# BackplanePowerSupply.net
KiCad netlist of a schematic drawn in EAGLE
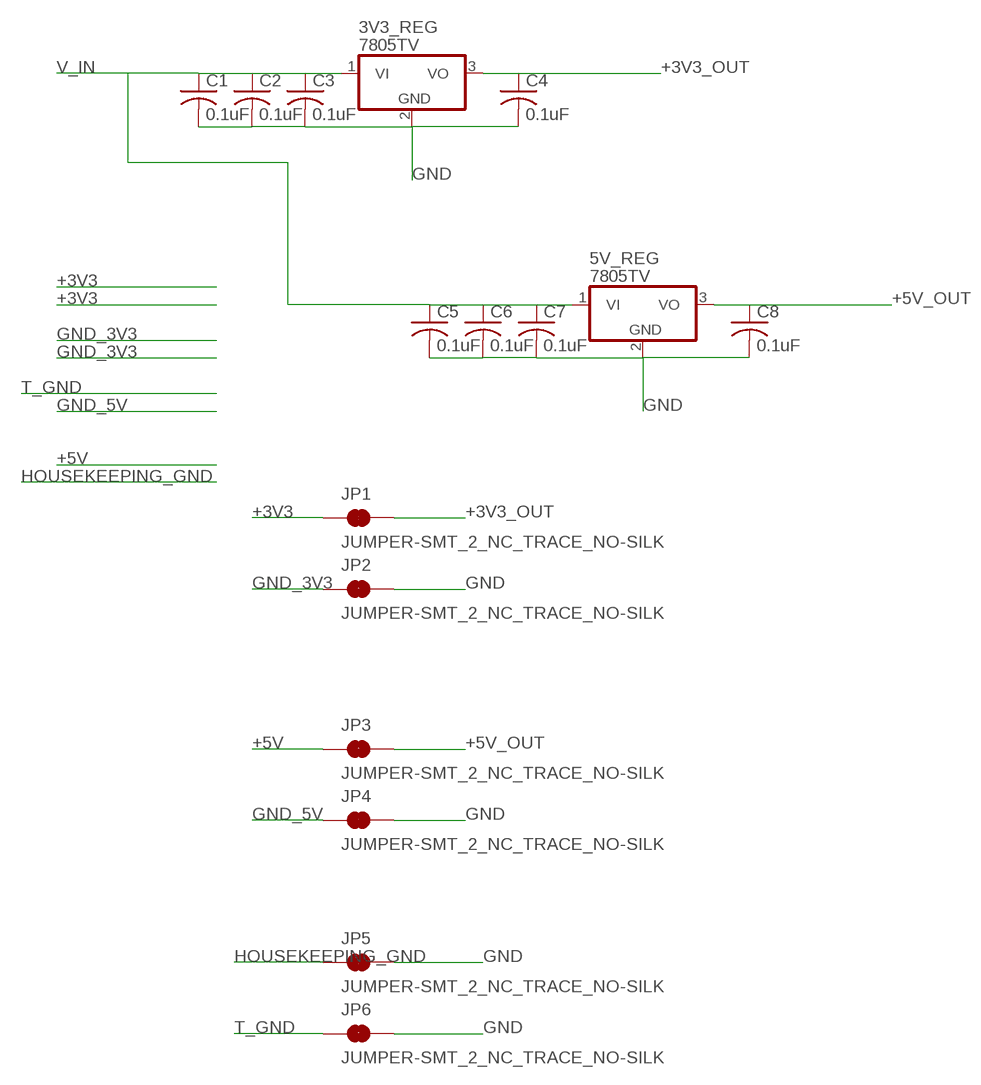
[diagram p0: schematic, sheet 1]

(export (version "E")
  (design (tool "Eeschema 10.0.6"))
  (components
    (comp (ref "3V3_REG")
      (value "7805TV")
      (footprint "eagle-import:TO220V")
      (libsource (lib "eagle-import") (part "78TV05"))
    )
    (comp (ref "5V_REG")
      (value "7805TV")
      (footprint "eagle-import:TO220V")
      (libsource (lib "eagle-import") (part "78TV05"))
    )
    (comp (ref "C1")
      (value "0.1uF")
      (footprint "eagle-import:C050-025X075")
      (libsource (lib "eagle-import") (part "C-US050-025X075"))
    )
    (comp (ref "C2")
      (value "0.1uF")
      (footprint "eagle-import:C050-025X075")
      (libsource (lib "eagle-import") (part "C-US050-025X075"))
    )
    (comp (ref "C3")
      (value "0.1uF")
      (footprint "eagle-import:C050-025X075")
      (libsource (lib "eagle-import") (part "C-US050-025X075"))
    )
    (comp (ref "C4")
      (value "0.1uF")
      (footprint "eagle-import:C050-025X075")
      (libsource (lib "eagle-import") (part "C-US050-025X075"))
    )
    (comp (ref "C5")
      (value "0.1uF")
      (footprint "eagle-import:C050-025X075")
      (libsource (lib "eagle-import") (part "C-US050-025X075"))
    )
    (comp (ref "C6")
      (value "0.1uF")
      (footprint "eagle-import:C050-025X075")
      (libsource (lib "eagle-import") (part "C-US050-025X075"))
    )
    (comp (ref "C7")
      (value "0.1uF")
      (footprint "eagle-import:C050-025X075")
      (libsource (lib "eagle-import") (part "C-US050-025X075"))
    )
    (comp (ref "C8")
      (value "0.1uF")
      (footprint "eagle-import:C050-025X075")
      (libsource (lib "eagle-import") (part "C-US050-025X075"))
    )
    (comp (ref "JP1")
      (value "JUMPER-SMT_2_NC_TRACE_NO-SILK")
      (footprint "eagle-import:SMT-JUMPER_2_NC_TRACE_NO-SILK")
      (libsource (lib "eagle-import") (part "JUMPER-SMT_2_NC_TRACE_NO-SILK"))
    )
    (comp (ref "JP2")
      (value "JUMPER-SMT_2_NC_TRACE_NO-SILK")
      (footprint "eagle-import:SMT-JUMPER_2_NC_TRACE_NO-SILK")
      (libsource (lib "eagle-import") (part "JUMPER-SMT_2_NC_TRACE_NO-SILK"))
    )
    (comp (ref "JP3")
      (value "JUMPER-SMT_2_NC_TRACE_NO-SILK")
      (footprint "eagle-import:SMT-JUMPER_2_NC_TRACE_NO-SILK")
      (libsource (lib "eagle-import") (part "JUMPER-SMT_2_NC_TRACE_NO-SILK"))
    )
    (comp (ref "JP4")
      (value "JUMPER-SMT_2_NC_TRACE_NO-SILK")
      (footprint "eagle-import:SMT-JUMPER_2_NC_TRACE_NO-SILK")
      (libsource (lib "eagle-import") (part "JUMPER-SMT_2_NC_TRACE_NO-SILK"))
    )
    (comp (ref "JP5")
      (value "JUMPER-SMT_2_NC_TRACE_NO-SILK")
      (footprint "eagle-import:SMT-JUMPER_2_NC_TRACE_NO-SILK")
      (libsource (lib "eagle-import") (part "JUMPER-SMT_2_NC_TRACE_NO-SILK"))
    )
    (comp (ref "JP6")
      (value "JUMPER-SMT_2_NC_TRACE_NO-SILK")
      (footprint "eagle-import:SMT-JUMPER_2_NC_TRACE_NO-SILK")
      (libsource (lib "eagle-import") (part "JUMPER-SMT_2_NC_TRACE_NO-SILK"))
    )
  )
  (nets
    (net (code "1") (name "/+3V3") (class "Default")
      (node (ref "JP1") (pin "1") (pinfunction "1_1") (pintype "passive"))
    )
    (net (code "2") (name "/+3V3_OUT") (class "Default")
      (node (ref "3V3_REG") (pin "3") (pinfunction "VO_3") (pintype "passive"))
      (node (ref "C4") (pin "1") (pinfunction "1_1") (pintype "passive"))
      (node (ref "JP1") (pin "2") (pinfunction "2_2") (pintype "passive"))
    )
    (net (code "3") (name "/+5V") (class "Default")
      (node (ref "JP3") (pin "1") (pinfunction "1_1") (pintype "passive"))
    )
    (net (code "4") (name "/+5V_OUT") (class "Default")
      (node (ref "5V_REG") (pin "3") (pinfunction "VO_3") (pintype "passive"))
      (node (ref "C8") (pin "1") (pinfunction "1_1") (pintype "passive"))
      (node (ref "JP3") (pin "2") (pinfunction "2_2") (pintype "passive"))
    )
    (net (code "5") (name "/GND") (class "Default")
      (node (ref "3V3_REG") (pin "2") (pinfunction "GND_2") (pintype "passive"))
      (node (ref "5V_REG") (pin "2") (pinfunction "GND_2") (pintype "passive"))
      (node (ref "C1") (pin "2") (pinfunction "2_2") (pintype "passive"))
      (node (ref "C2") (pin "2") (pinfunction "2_2") (pintype "passive"))
      (node (ref "C3") (pin "2") (pinfunction "2_2") (pintype "passive"))
      (node (ref "C4") (pin "2") (pinfunction "2_2") (pintype "passive"))
      (node (ref "C5") (pin "2") (pinfunction "2_2") (pintype "passive"))
      (node (ref "C6") (pin "2") (pinfunction "2_2") (pintype "passive"))
      (node (ref "C7") (pin "2") (pinfunction "2_2") (pintype "passive"))
      (node (ref "C8") (pin "2") (pinfunction "2_2") (pintype "passive"))
      (node (ref "JP2") (pin "2") (pinfunction "2_2") (pintype "passive"))
      (node (ref "JP4") (pin "2") (pinfunction "2_2") (pintype "passive"))
      (node (ref "JP5") (pin "2") (pinfunction "2_2") (pintype "passive"))
      (node (ref "JP6") (pin "2") (pinfunction "2_2") (pintype "passive"))
    )
    (net (code "6") (name "/GND_3V3") (class "Default")
      (node (ref "JP2") (pin "1") (pinfunction "1_1") (pintype "passive"))
    )
    (net (code "7") (name "/GND_5V") (class "Default")
      (node (ref "JP4") (pin "1") (pinfunction "1_1") (pintype "passive"))
    )
    (net (code "8") (name "/HOUSEKEEPING_GND") (class "Default")
      (node (ref "JP5") (pin "1") (pinfunction "1_1") (pintype "passive"))
    )
    (net (code "9") (name "/T_GND") (class "Default")
      (node (ref "JP6") (pin "1") (pinfunction "1_1") (pintype "passive"))
    )
    (net (code "10") (name "/V_IN") (class "Default")
      (node (ref "3V3_REG") (pin "1") (pinfunction "VI_1") (pintype "input"))
      (node (ref "5V_REG") (pin "1") (pinfunction "VI_1") (pintype "input"))
      (node (ref "C1") (pin "1") (pinfunction "1_1") (pintype "passive"))
      (node (ref "C2") (pin "1") (pinfunction "1_1") (pintype "passive"))
      (node (ref "C3") (pin "1") (pinfunction "1_1") (pintype "passive"))
      (node (ref "C5") (pin "1") (pinfunction "1_1") (pintype "passive"))
      (node (ref "C6") (pin "1") (pinfunction "1_1") (pintype "passive"))
      (node (ref "C7") (pin "1") (pinfunction "1_1") (pintype "passive"))
    )
  )
)
